# LEDS.net
KiCad netlist of a schematic drawn in Altium Designer
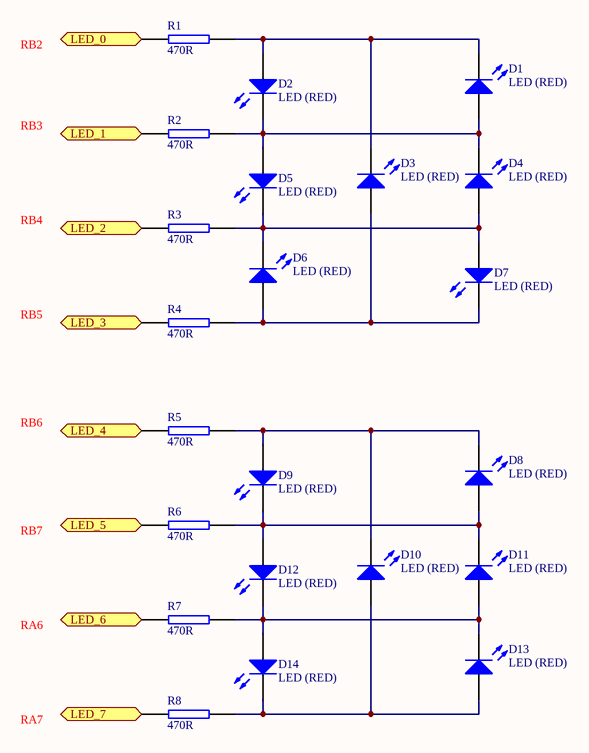
[diagram p0: LEDS.SchDoc]

(export (version "E")
  (design (tool "Eeschema 10.0.6"))
  (components
    (comp (ref "D1")
      (value "LED (RED)")
      (footprint "PLCC_2")
      (description "3mm RED LED")
      (libsource (lib "NASCO") (part "LED 3mm RED"))
    )
    (comp (ref "D2")
      (value "LED (RED)")
      (footprint "PLCC_2")
      (description "3mm RED LED")
      (libsource (lib "NASCO") (part "LED 3mm RED"))
    )
    (comp (ref "D3")
      (value "LED (RED)")
      (footprint "PLCC_2")
      (description "3mm RED LED")
      (libsource (lib "NASCO") (part "LED 3mm RED"))
    )
    (comp (ref "D4")
      (value "LED (RED)")
      (footprint "PLCC_2")
      (description "3mm RED LED")
      (libsource (lib "NASCO") (part "LED 3mm RED"))
    )
    (comp (ref "D5")
      (value "LED (RED)")
      (footprint "PLCC_2")
      (description "3mm RED LED")
      (libsource (lib "NASCO") (part "LED 3mm RED"))
    )
    (comp (ref "D6")
      (value "LED (RED)")
      (footprint "PLCC_2")
      (description "3mm RED LED")
      (libsource (lib "NASCO") (part "LED 3mm RED"))
    )
    (comp (ref "D7")
      (value "LED (RED)")
      (footprint "PLCC_2")
      (description "3mm RED LED")
      (libsource (lib "NASCO") (part "LED 3mm RED"))
    )
    (comp (ref "D8")
      (value "LED (RED)")
      (footprint "PLCC_2")
      (description "3mm RED LED")
      (libsource (lib "NASCO") (part "LED 3mm RED"))
    )
    (comp (ref "D9")
      (value "LED (RED)")
      (footprint "PLCC_2")
      (description "3mm RED LED")
      (libsource (lib "NASCO") (part "LED 3mm RED"))
    )
    (comp (ref "D10")
      (value "LED (RED)")
      (footprint "PLCC_2")
      (description "3mm RED LED")
      (libsource (lib "NASCO") (part "LED 3mm RED"))
    )
    (comp (ref "D11")
      (value "LED (RED)")
      (footprint "PLCC_2")
      (description "3mm RED LED")
      (libsource (lib "NASCO") (part "LED 3mm RED"))
    )
    (comp (ref "D12")
      (value "LED (RED)")
      (footprint "PLCC_2")
      (description "3mm RED LED")
      (libsource (lib "NASCO") (part "LED 3mm RED"))
    )
    (comp (ref "D13")
      (value "LED (RED)")
      (footprint "PLCC_2")
      (description "3mm RED LED")
      (libsource (lib "NASCO") (part "LED 3mm RED"))
    )
    (comp (ref "D14")
      (value "LED (RED)")
      (footprint "PLCC_2")
      (description "3mm RED LED")
      (libsource (lib "NASCO") (part "LED 3mm RED"))
    )
    (comp (ref "R1")
      (value "470R")
      (footprint "RES (3D) - 0603")
      (description "RESISTOR SMD 0603 590R")
      (libsource (lib "NASCO Resistors") (part "RES SMD 0603 590R"))
    )
    (comp (ref "R2")
      (value "470R")
      (footprint "RES (3D) - 0603")
      (description "RESISTOR SMD 0603 590R")
      (libsource (lib "NASCO Resistors") (part "RES SMD 0603 590R"))
    )
    (comp (ref "R3")
      (value "470R")
      (footprint "RES (3D) - 0603")
      (description "RESISTOR SMD 0603 590R")
      (libsource (lib "NASCO Resistors") (part "RES SMD 0603 590R"))
    )
    (comp (ref "R4")
      (value "470R")
      (footprint "RES (3D) - 0603")
      (description "RESISTOR SMD 0603 590R")
      (libsource (lib "NASCO Resistors") (part "RES SMD 0603 590R"))
    )
    (comp (ref "R5")
      (value "470R")
      (footprint "RES (3D) - 0603")
      (description "RESISTOR SMD 0603 590R")
      (libsource (lib "NASCO Resistors") (part "RES SMD 0603 590R"))
    )
    (comp (ref "R6")
      (value "470R")
      (footprint "RES (3D) - 0603")
      (description "RESISTOR SMD 0603 590R")
      (libsource (lib "NASCO Resistors") (part "RES SMD 0603 590R"))
    )
    (comp (ref "R7")
      (value "470R")
      (footprint "RES (3D) - 0603")
      (description "RESISTOR SMD 0603 590R")
      (libsource (lib "NASCO Resistors") (part "RES SMD 0603 590R"))
    )
    (comp (ref "R8")
      (value "470R")
      (footprint "RES (3D) - 0603")
      (description "RESISTOR SMD 0603 590R")
      (libsource (lib "NASCO Resistors") (part "RES SMD 0603 590R"))
    )
  )
  (nets
    (net (code "1") (name "/LED_0") (class "Default")
      (node (ref "R1") (pin "1") (pinfunction "1_1") (pintype "passive"))
    )
    (net (code "2") (name "/LED_1") (class "Default")
      (node (ref "R2") (pin "1") (pinfunction "1_1") (pintype "passive"))
    )
    (net (code "3") (name "/LED_2") (class "Default")
      (node (ref "R3") (pin "1") (pinfunction "1_1") (pintype "passive"))
    )
    (net (code "4") (name "/LED_3") (class "Default")
      (node (ref "R4") (pin "1") (pinfunction "1_1") (pintype "passive"))
    )
    (net (code "5") (name "/LED_4") (class "Default")
      (node (ref "R5") (pin "1") (pinfunction "1_1") (pintype "passive"))
    )
    (net (code "6") (name "/LED_5") (class "Default")
      (node (ref "R6") (pin "1") (pinfunction "1_1") (pintype "passive"))
    )
    (net (code "7") (name "/LED_6") (class "Default")
      (node (ref "R7") (pin "1") (pinfunction "1_1") (pintype "passive"))
    )
    (net (code "8") (name "/LED_7") (class "Default")
      (node (ref "R8") (pin "1") (pinfunction "1_1") (pintype "passive"))
    )
    (net (code "9") (name "Net-(D1-A)") (class "Default")
      (node (ref "D1") (pin "1") (pinfunction "A_1") (pintype "passive"))
      (node (ref "D2") (pin "2") (pinfunction "K_2") (pintype "passive"))
      (node (ref "D4") (pin "2") (pinfunction "K_2") (pintype "passive"))
      (node (ref "D5") (pin "1") (pinfunction "A_1") (pintype "passive"))
      (node (ref "R2") (pin "2") (pinfunction "2_2") (pintype "passive"))
    )
    (net (code "10") (name "Net-(D1-K)") (class "Default")
      (node (ref "D1") (pin "2") (pinfunction "K_2") (pintype "passive"))
      (node (ref "D2") (pin "1") (pinfunction "A_1") (pintype "passive"))
      (node (ref "D3") (pin "2") (pinfunction "K_2") (pintype "passive"))
      (node (ref "R1") (pin "2") (pinfunction "2_2") (pintype "passive"))
    )
    (net (code "11") (name "Net-(D3-A)") (class "Default")
      (node (ref "D3") (pin "1") (pinfunction "A_1") (pintype "passive"))
      (node (ref "D6") (pin "1") (pinfunction "A_1") (pintype "passive"))
      (node (ref "D7") (pin "2") (pinfunction "K_2") (pintype "passive"))
      (node (ref "R4") (pin "2") (pinfunction "2_2") (pintype "passive"))
    )
    (net (code "12") (name "Net-(D4-A)") (class "Default")
      (node (ref "D4") (pin "1") (pinfunction "A_1") (pintype "passive"))
      (node (ref "D5") (pin "2") (pinfunction "K_2") (pintype "passive"))
      (node (ref "D6") (pin "2") (pinfunction "K_2") (pintype "passive"))
      (node (ref "D7") (pin "1") (pinfunction "A_1") (pintype "passive"))
      (node (ref "R3") (pin "2") (pinfunction "2_2") (pintype "passive"))
    )
    (net (code "13") (name "Net-(D10-A)") (class "Default")
      (node (ref "D10") (pin "1") (pinfunction "A_1") (pintype "passive"))
      (node (ref "D13") (pin "1") (pinfunction "A_1") (pintype "passive"))
      (node (ref "D14") (pin "2") (pinfunction "K_2") (pintype "passive"))
      (node (ref "R8") (pin "2") (pinfunction "2_2") (pintype "passive"))
    )
    (net (code "14") (name "Net-(D10-K)") (class "Default")
      (node (ref "D10") (pin "2") (pinfunction "K_2") (pintype "passive"))
      (node (ref "D8") (pin "2") (pinfunction "K_2") (pintype "passive"))
      (node (ref "D9") (pin "1") (pinfunction "A_1") (pintype "passive"))
      (node (ref "R5") (pin "2") (pinfunction "2_2") (pintype "passive"))
    )
    (net (code "15") (name "Net-(D11-A)") (class "Default")
      (node (ref "D11") (pin "1") (pinfunction "A_1") (pintype "passive"))
      (node (ref "D12") (pin "2") (pinfunction "K_2") (pintype "passive"))
      (node (ref "D13") (pin "2") (pinfunction "K_2") (pintype "passive"))
      (node (ref "D14") (pin "1") (pinfunction "A_1") (pintype "passive"))
      (node (ref "R7") (pin "2") (pinfunction "2_2") (pintype "passive"))
    )
    (net (code "16") (name "Net-(D11-K)") (class "Default")
      (node (ref "D11") (pin "2") (pinfunction "K_2") (pintype "passive"))
      (node (ref "D12") (pin "1") (pinfunction "A_1") (pintype "passive"))
      (node (ref "D8") (pin "1") (pinfunction "A_1") (pintype "passive"))
      (node (ref "D9") (pin "2") (pinfunction "K_2") (pintype "passive"))
      (node (ref "R6") (pin "2") (pinfunction "2_2") (pintype "passive"))
    )
  )
)
